# Main.net
KiCad netlist of a schematic drawn in Altium Designer
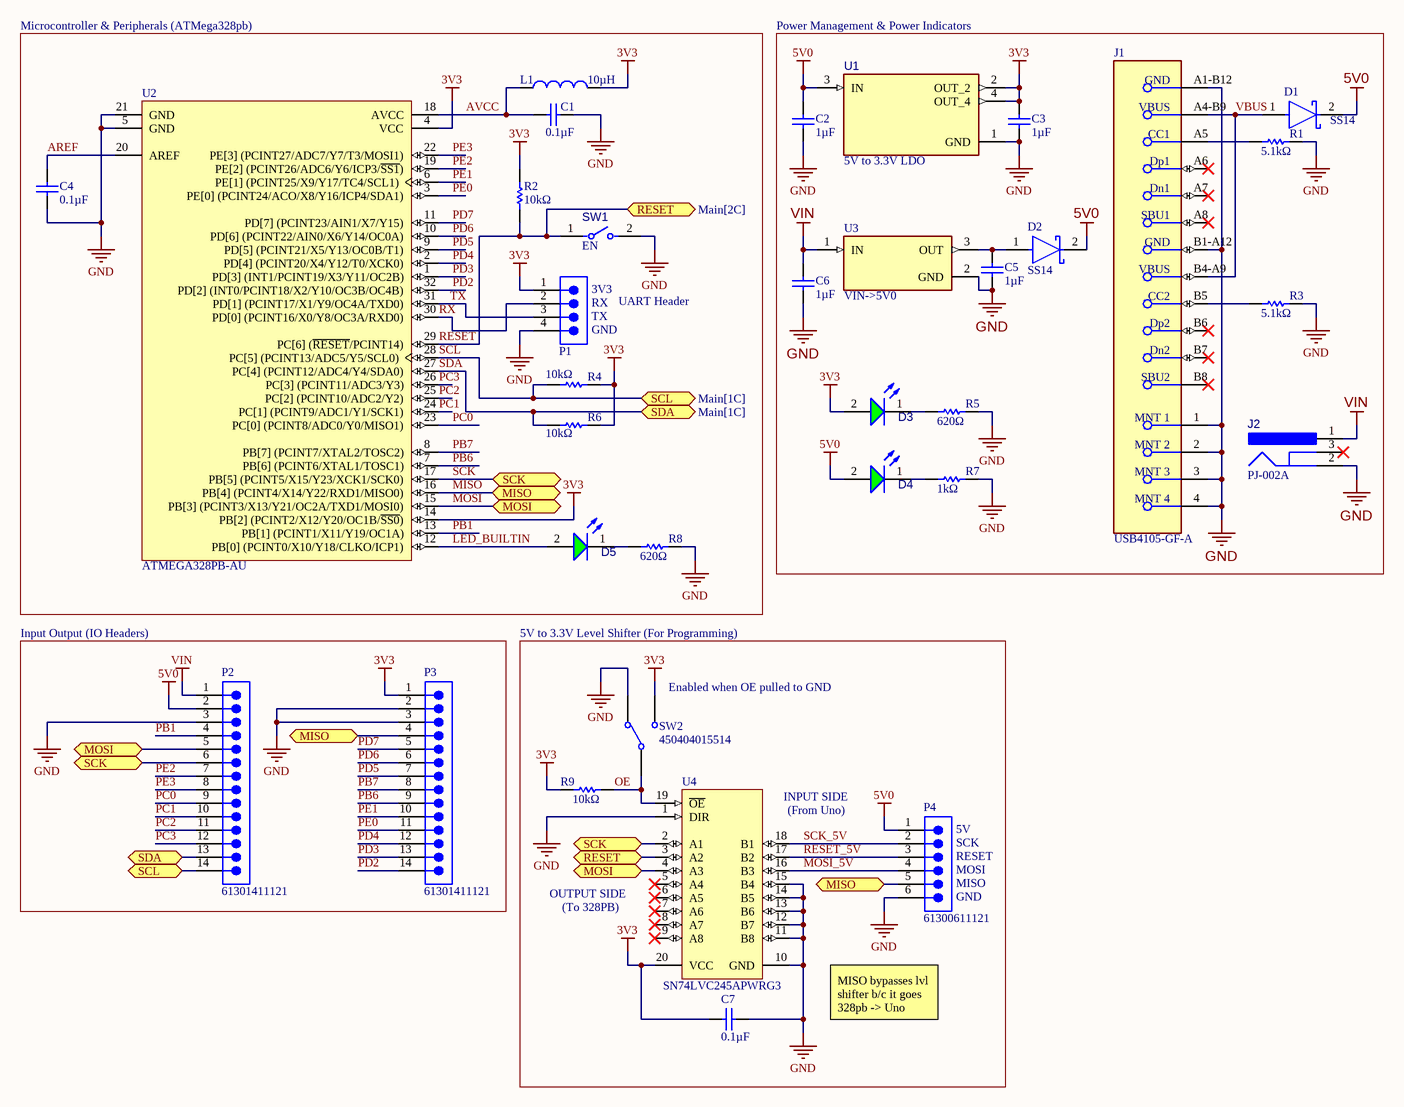
[diagram p0: Main.SchDoc]

(export (version "E")
  (design (tool "Eeschema 10.0.6"))
  (components
    (comp (ref "C1")
      (value "0.1µF")
      (footprint "CAPC3216X100X50LL20T25")
      (description "Chip Capacitor, 100 nF, +/- 10%, 25 V, -55 to 125 degC, 1206 (3216 Metric), RoHS, Tape and Reel")
      (fields (field (name "MANUFACTURER") "Kemet"))
      (libsource (lib "") (part "CAP-NP-2_1"))
    )
    (comp (ref "C2")
      (value "1µF")
      (footprint "CAPC3216X110X50LL20T25")
      (description "Chip Capacitor, 1 uF, +/- 10%, 50 V, -55 to 125 degC, 1206 (3216 Metric), RoHS, Tape and Reel")
      (fields (field (name "MANUFACTURER") "Kemet") (field (name "TOLERANCE") "10%"))
      (libsource (lib "Altium Content Vault") (part "CAP-NP-2"))
    )
    (comp (ref "C3")
      (value "1µF")
      (footprint "CAPC3216X110X50LL20T25")
      (description "Chip Capacitor, 1 uF, +/- 10%, 50 V, -55 to 125 degC, 1206 (3216 Metric), RoHS, Tape and Reel")
      (fields (field (name "MANUFACTURER") "Kemet") (field (name "TOLERANCE") "10%"))
      (libsource (lib "Altium Content Vault") (part "CAP-NP-2"))
    )
    (comp (ref "C4")
      (value "0.1µF")
      (footprint "CAPC3216X100X50LL20T25")
      (description "Chip Capacitor, 100 nF, +/- 10%, 25 V, -55 to 125 degC, 1206 (3216 Metric), RoHS, Tape and Reel")
      (fields (field (name "MANUFACTURER") "Kemet"))
      (libsource (lib "") (part "CAP-NP-2_1"))
    )
    (comp (ref "C5")
      (value "1µF")
      (footprint "CAPC3216X110X50LL20T25")
      (description "Chip Capacitor, 1 uF, +/- 10%, 50 V, -55 to 125 degC, 1206 (3216 Metric), RoHS, Tape and Reel")
      (fields (field (name "MANUFACTURER") "Kemet") (field (name "TOLERANCE") "10%"))
      (libsource (lib "Altium Content Vault") (part "CAP-NP-2"))
    )
    (comp (ref "C6")
      (value "1µF")
      (footprint "CAPC3216X110X50LL20T25")
      (description "Chip Capacitor, 1 uF, +/- 10%, 50 V, -55 to 125 degC, 1206 (3216 Metric), RoHS, Tape and Reel")
      (fields (field (name "MANUFACTURER") "Kemet") (field (name "TOLERANCE") "10%"))
      (libsource (lib "Altium Content Vault") (part "CAP-NP-2"))
    )
    (comp (ref "C7")
      (value "0.1µF")
      (footprint "CAPC3216X100X50LL20T25")
      (description "Chip Capacitor, 100 nF, +/- 10%, 25 V, -55 to 125 degC, 1206 (3216 Metric), RoHS, Tape and Reel")
      (fields (field (name "MANUFACTURER") "Kemet"))
      (libsource (lib "") (part "CAP-NP-2_1"))
    )
    (comp (ref "D1")
      (value "SS14")
      (footprint "FP-403AE-MFG")
      (description "DIODE SCHOTTKY 40V 1A SMA")
      (fields
        (field (name "MANUFACTURER") "ON Semiconductor")
        (field (name "OCTOPART") "https://octopart.com/ss14-on+semiconductor-29205033")
      )
      (libsource (lib "Altium Content Vault") (part "360ad2f4ac25a952324d13796385471"))
    )
    (comp (ref "D2")
      (value "SS14")
      (footprint "FP-403AE-MFG")
      (description "DIODE SCHOTTKY 40V 1A SMA")
      (fields
        (field (name "MANUFACTURER") "ON Semiconductor")
        (field (name "OCTOPART") "https://octopart.com/ss14-on+semiconductor-29205033")
      )
      (libsource (lib "Altium Content Vault") (part "360ad2f4ac25a952324d13796385471"))
    )
    (comp (ref "D3")
      (value "150120GS75000")
      (footprint "WL-SMCW_1206_150120xx75000")
      (description "WL-SMCW SMT Mono-Color Chip LED Waterclear")
      (libsource (lib "Altium Content Vault") (part "LED_Green_2A-1K"))
    )
    (comp (ref "D4")
      (value "150120GS75000")
      (footprint "WL-SMCW_1206_150120xx75000")
      (description "WL-SMCW SMT Mono-Color Chip LED Waterclear")
      (libsource (lib "Altium Content Vault") (part "LED_Green_2A-1K"))
    )
    (comp (ref "D5")
      (value "150120GS75000")
      (footprint "WL-SMCW_1206_150120xx75000")
      (description "WL-SMCW SMT Mono-Color Chip LED Waterclear")
      (libsource (lib "Altium Content Vault") (part "LED_Green_2A-1K"))
    )
    (comp (ref "J1")
      (value "USB4105-GF-A")
      (footprint "FP-USB4105-GF-A-MFG")
      (description "CONN RCPT USB2.0 TYPEC 5A")
      (fields
        (field (name "MANUFACTURER") "GCT")
        (field (name "OCTOPART") "https://octopart.com/usb4105-gf-a-gct-106627878")
      )
      (libsource (lib "Altium Content Vault") (part "e7c17a616881a82b79941196b4bec10"))
    )
    (comp (ref "J2")
      (value "PJ-002A")
      (footprint "CUI-PJ-002A_V")
      (fields (field (name "MANUFACTURER") "CUIInc."))
      (libsource (lib "Altium Content Vault") (part "JACK-2CD3-RN_B"))
    )
    (comp (ref "L1")
      (value "10µH")
      (footprint "WE-MI_1206_L3.2W1.6H1.1")
      (fields (field (name "TOLERANCE") "10%"))
      (libsource (lib "Altium Content Vault") (part "Inductor - 1"))
    )
    (comp (ref "P1")
      (value "61300411121")
      (footprint "61300411121")
      (description "WR-PHD Pin Header, THT, Vertical, pitch 2.54mm, 1 Row, 4P")
      (fields (field (name "MANUFACTURER") "Wurth Elektronik"))
      (libsource (lib "Altium_WR-PHD_rev24a") (part "61300411121"))
    )
    (comp (ref "P2")
      (value "61301411121")
      (footprint "61301411121")
      (libsource (lib "Altium Content Vault") (part "Header_Male_1R_14P"))
    )
    (comp (ref "P3")
      (value "61301411121")
      (footprint "61301411121")
      (libsource (lib "Altium Content Vault") (part "Header_Male_1R_14P"))
    )
    (comp (ref "P4")
      (value "61300611121")
      (footprint "61300611121")
      (libsource (lib "Altium Content Vault") (part "Header_Male_1R_06P"))
    )
    (comp (ref "R1")
      (value "5.1kΩ")
      (footprint "RESC3116X65X40LL10T20")
      (fields (field (name "MANUFACTURER") "Yageo") (field (name "PART NUMBER") "RC1206JR-075K1L"))
      (libsource (lib "Altium Content Vault") (part "RES"))
    )
    (comp (ref "R2")
      (value "10kΩ")
      (footprint "RESC3116X65X40LL10T20")
      (description "Chip Resistor, 10 KOhm, +/- 1%, 0.25 W, -55 to 155 degC, 1206 (3216 Metric), RoHS, Tape and Reel")
      (fields (field (name "TOLERANCE") "1%") (field (name "MANUFACTURER") "Yageo"))
      (libsource (lib "Altium Content Vault") (part "RES-2"))
    )
    (comp (ref "R3")
      (value "5.1kΩ")
      (footprint "RESC3116X65X40LL10T20")
      (fields (field (name "MANUFACTURER") "Yageo") (field (name "PART NUMBER") "RC1206JR-075K1L"))
      (libsource (lib "Altium Content Vault") (part "RES"))
    )
    (comp (ref "R4")
      (value "10kΩ")
      (footprint "RESC3116X65X40LL10T20")
      (description "Chip Resistor, 10 KOhm, +/- 1%, 0.25 W, -55 to 155 degC, 1206 (3216 Metric), RoHS, Tape and Reel")
      (fields (field (name "TOLERANCE") "1%") (field (name "MANUFACTURER") "Yageo"))
      (libsource (lib "Altium Content Vault") (part "RES-2"))
    )
    (comp (ref "R5")
      (value "620Ω")
      (footprint "RESC3116X65X40LL10T20")
      (fields (field (name "PART NUMBER") "RC1206JR-07620RL") (field (name "MANUFACTURER") "Yageo"))
      (libsource (lib "Altium Content Vault") (part "RES"))
    )
    (comp (ref "R6")
      (value "10kΩ")
      (footprint "RESC3116X65X40LL10T20")
      (description "Chip Resistor, 10 KOhm, +/- 1%, 0.25 W, -55 to 155 degC, 1206 (3216 Metric), RoHS, Tape and Reel")
      (fields (field (name "TOLERANCE") "1%") (field (name "MANUFACTURER") "Yageo"))
      (libsource (lib "Altium Content Vault") (part "RES-2"))
    )
    (comp (ref "R7")
      (value "1kΩ")
      (footprint "RESC3116X65X40LL10T20")
      (description "Chip Resistor, 1 KOhm, +/- 1%, 0.25 W, -55 to 155 degC, 1206 (3216 Metric), RoHS, Tape and Reel")
      (fields (field (name "TOLERANCE") "1%") (field (name "MANUFACTURER") "Yageo"))
      (libsource (lib "Altium Content Vault") (part "RES-2"))
    )
    (comp (ref "R8")
      (value "620Ω")
      (footprint "RESC3116X65X40LL10T20")
      (fields (field (name "PART NUMBER") "RC1206JR-07620RL") (field (name "MANUFACTURER") "Yageo"))
      (libsource (lib "Altium Content Vault") (part "RES"))
    )
    (comp (ref "R9")
      (value "10kΩ")
      (footprint "RESC3116X65X40LL10T20")
      (description "Chip Resistor, 10 KOhm, +/- 1%, 0.25 W, -55 to 155 degC, 1206 (3216 Metric), RoHS, Tape and Reel")
      (fields (field (name "TOLERANCE") "1%") (field (name "MANUFACTURER") "Yageo"))
      (libsource (lib "Altium Content Vault") (part "RES-2"))
    )
    (comp (ref "SW1")
      (value "EN")
      (footprint "FP-B3U-1000P-B-MFG")
      (description "SWITCH TACTILE SPST-NO 0.05A 12V")
      (fields
        (field (name "MANUFACTURER PART NUMBER") "B3U-1000P-B")
        (field (name "OCTOPART") "https://octopart.com/b3u-1000p-b-omron-1057356")
      )
      (libsource (lib "Altium Content Vault") (part "bb27bde45df87f1f469753f287ef5ae"))
    )
    (comp (ref "SW2")
      (value "450404015514")
      (footprint "450404015514")
      (description "450404015514 Slide Switch, 0.3A, 5Vdc, Smd Rohs Compliant: Yes")
      (libsource (lib "Altium Content Vault") (part "SPDT"))
    )
    (comp (ref "U1")
      (value "TLV1117LV33DCYR")
      (footprint "VREG_TLV1117LV33DCYR")
      (description "1-A, low-dropout voltage regulator")
      (fields (field (name "DIGI-KEY_PART_NUMBER") "296-28778-2-ND") (field (name "MF") "Texas Instruments"))
      (libsource (lib "TLV1117LV33DCYR") (part "TLV1117LV33DCYR"))
    )
    (comp (ref "U2")
      (value "ATMEGA328PB-AU")
      (footprint "ATML-32A_L")
      (fields (field (name "MANUFACTURER") "Microchip"))
      (libsource (lib "Altium Content Vault") (part "ATML-ATMEGA328PB-32A"))
    )
    (comp (ref "U3")
      (value "VIN->5V0")
      (footprint "DPAK229P990X238-4N")
      (description "Linear Voltage Regulator IC 1 Output 1A DPAK")
      (fields (field (name "MP") "MC7805BDTRKG") (field (name "MF") "ON Semiconductor"))
      (libsource (lib "MC7805BDTRKG") (part "MC7805BDTRKG"))
    )
    (comp (ref "U4")
      (value "SN74LVC245APWRG3")
      (footprint "PW0020A_N")
      (description "Octal Bus Transceiver With 3-State Outputs, PW0020A, LARGE T&R")
      (fields
        (field (name "MANUFACTURER") "Texas Instruments")
        (field (name "GENERIC PART NUMBER") "SN74LVC245A")
      )
      (libsource (lib "Altium Content Vault") (part "TI-SN_CDX4XXXXXX245XX_6XXX-20"))
    )
  )
  (nets
    (net (code "1") (name "/AREF") (class "Default")
      (node (ref "C4") (pin "1") (pinfunction "1_1") (pintype "passive"))
      (node (ref "U2") (pin "20") (pinfunction "AREF_20") (pintype "passive"))
    )
    (net (code "2") (name "/AVCC") (class "Default")
      (node (ref "C1") (pin "2") (pinfunction "2_2") (pintype "passive"))
      (node (ref "L1") (pin "1") (pinfunction "1_1") (pintype "passive"))
      (node (ref "U2") (pin "18") (pinfunction "AVCC_18") (pintype "power_in"))
    )
    (net (code "3") (name "/LED_BUILTIN") (class "Default")
      (node (ref "D5") (pin "2") (pinfunction "A_2") (pintype "passive"))
      (node (ref "U2") (pin "12") (pinfunction "PB[0]_(PCINT0/X10/Y18/CLKO/ICP1)_12") (pintype "bidirectional"))
    )
    (net (code "4") (name "/MISO") (class "Default")
      (node (ref "P3") (pin "4") (pinfunction "4_4") (pintype "passive"))
      (node (ref "P4") (pin "5") (pinfunction "5_5") (pintype "passive"))
      (node (ref "U2") (pin "16") (pinfunction "PB[4]_(PCINT4/X14/Y22/RXD1/MISO0)_16") (pintype "bidirectional"))
    )
    (net (code "5") (name "/MOSI") (class "Default")
      (node (ref "P2") (pin "5") (pinfunction "5_5") (pintype "passive"))
      (node (ref "U2") (pin "15") (pinfunction "PB[3]_(PCINT3/X13/Y21/OC2A/TXD1/MOSI0)_15") (pintype "bidirectional"))
      (node (ref "U4") (pin "4") (pinfunction "A3_4") (pintype "bidirectional"))
    )
    (net (code "6") (name "/MOSI_5V") (class "Default")
      (node (ref "P4") (pin "4") (pinfunction "4_4") (pintype "passive"))
      (node (ref "U4") (pin "16") (pinfunction "B3_16") (pintype "bidirectional"))
    )
    (net (code "7") (name "/OE") (class "Default")
      (node (ref "R9") (pin "1") (pinfunction "1_1") (pintype "passive"))
      (node (ref "SW2") (pin "COM") (pinfunction "COM_COM") (pintype "passive"))
      (node (ref "U4") (pin "19") (pinfunction "~{OE}_19") (pintype "input"))
    )
    (net (code "8") (name "/PB1") (class "Default")
      (node (ref "P2") (pin "4") (pinfunction "4_4") (pintype "passive"))
      (node (ref "U2") (pin "13") (pinfunction "PB[1]_(PCINT1/X11/Y19/OC1A)_13") (pintype "bidirectional"))
    )
    (net (code "9") (name "/PB6") (class "Default")
      (node (ref "P3") (pin "9") (pinfunction "9_9") (pintype "passive"))
      (node (ref "U2") (pin "7") (pinfunction "PB[6]_(PCINT6/XTAL1/TOSC1)_7") (pintype "bidirectional"))
    )
    (net (code "10") (name "/PB7") (class "Default")
      (node (ref "P3") (pin "8") (pinfunction "8_8") (pintype "passive"))
      (node (ref "U2") (pin "8") (pinfunction "PB[7]_(PCINT7/XTAL2/TOSC2)_8") (pintype "bidirectional"))
    )
    (net (code "11") (name "/PC0") (class "Default")
      (node (ref "P2") (pin "9") (pinfunction "9_9") (pintype "passive"))
      (node (ref "U2") (pin "23") (pinfunction "PC[0]_(PCINT8/ADC0/Y0/MISO1)_23") (pintype "bidirectional"))
    )
    (net (code "12") (name "/PC1") (class "Default")
      (node (ref "P2") (pin "10") (pinfunction "10_10") (pintype "passive"))
      (node (ref "U2") (pin "24") (pinfunction "PC[1]_(PCINT9/ADC1/Y1/SCK1)_24") (pintype "bidirectional"))
    )
    (net (code "13") (name "/PC2") (class "Default")
      (node (ref "P2") (pin "11") (pinfunction "11_11") (pintype "passive"))
      (node (ref "U2") (pin "25") (pinfunction "PC[2]_(PCINT10/ADC2/Y2)_25") (pintype "bidirectional"))
    )
    (net (code "14") (name "/PC3") (class "Default")
      (node (ref "P2") (pin "12") (pinfunction "12_12") (pintype "passive"))
      (node (ref "U2") (pin "26") (pinfunction "PC[3]_(PCINT11/ADC3/Y3)_26") (pintype "bidirectional"))
    )
    (net (code "15") (name "/PD2") (class "Default")
      (node (ref "P3") (pin "14") (pinfunction "14_14") (pintype "passive"))
      (node (ref "U2") (pin "32") (pinfunction "PD[2]_(INT0/PCINT18/X2/Y10/OC3B/OC4B)_32") (pintype "bidirectional"))
    )
    (net (code "16") (name "/PD3") (class "Default")
      (node (ref "P3") (pin "13") (pinfunction "13_13") (pintype "passive"))
      (node (ref "U2") (pin "1") (pinfunction "PD[3]_(INT1/PCINT19/X3/Y11/OC2B)_1") (pintype "bidirectional"))
    )
    (net (code "17") (name "/PD4") (class "Default")
      (node (ref "P3") (pin "12") (pinfunction "12_12") (pintype "passive"))
      (node (ref "U2") (pin "2") (pinfunction "PD[4]_(PCINT20/X4/Y12/T0/XCK0)_2") (pintype "bidirectional"))
    )
    (net (code "18") (name "/PD5") (class "Default")
      (node (ref "P3") (pin "7") (pinfunction "7_7") (pintype "passive"))
      (node (ref "U2") (pin "9") (pinfunction "PD[5]_(PCINT21/X5/Y13/OC0B/T1)_9") (pintype "bidirectional"))
    )
    (net (code "19") (name "/PD6") (class "Default")
      (node (ref "P3") (pin "6") (pinfunction "6_6") (pintype "passive"))
      (node (ref "U2") (pin "10") (pinfunction "PD[6]_(PCINT22/AIN0/X6/Y14/OC0A)_10") (pintype "bidirectional"))
    )
    (net (code "20") (name "/PD7") (class "Default")
      (node (ref "P3") (pin "5") (pinfunction "5_5") (pintype "passive"))
      (node (ref "U2") (pin "11") (pinfunction "PD[7]_(PCINT23/AIN1/X7/Y15)_11") (pintype "bidirectional"))
    )
    (net (code "21") (name "/PE0") (class "Default")
      (node (ref "P3") (pin "11") (pinfunction "11_11") (pintype "passive"))
      (node (ref "U2") (pin "3") (pinfunction "PE[0]_(PCINT24/ACO/X8/Y16/ICP4/SDA1)_3") (pintype "bidirectional"))
    )
    (net (code "22") (name "/PE1") (class "Default")
      (node (ref "P3") (pin "10") (pinfunction "10_10") (pintype "passive"))
      (node (ref "U2") (pin "6") (pinfunction "PE[1]_(PCINT25/X9/Y17/TC4/SCL1)_6") (pintype "bidirectional"))
    )
    (net (code "23") (name "/PE2") (class "Default")
      (node (ref "P2") (pin "7") (pinfunction "7_7") (pintype "passive"))
      (node (ref "U2") (pin "19") (pinfunction "PE[2]_(PCINT26/ADC6/Y6/ICP3/~{SS1})_19") (pintype "bidirectional"))
    )
    (net (code "24") (name "/PE3") (class "Default")
      (node (ref "P2") (pin "8") (pinfunction "8_8") (pintype "passive"))
      (node (ref "U2") (pin "22") (pinfunction "PE[3]_(PCINT27/ADC7/Y7/T3/MOSI1)_22") (pintype "bidirectional"))
    )
    (net (code "25") (name "/RESET") (class "Default")
      (node (ref "R2") (pin "1") (pinfunction "1_1") (pintype "passive"))
      (node (ref "SW1") (pin "1") (pinfunction "1_1") (pintype "passive"))
      (node (ref "U2") (pin "29") (pinfunction "PC[6]_(~{RESET}/PCINT14)_29") (pintype "bidirectional"))
      (node (ref "U4") (pin "3") (pinfunction "A2_3") (pintype "bidirectional"))
    )
    (net (code "26") (name "/RESET_5V") (class "Default")
      (node (ref "P4") (pin "3") (pinfunction "3_3") (pintype "passive"))
      (node (ref "U4") (pin "17") (pinfunction "B2_17") (pintype "bidirectional"))
    )
    (net (code "27") (name "/RX") (class "Default")
      (node (ref "P1") (pin "2") (pinfunction "2_2") (pintype "passive"))
      (node (ref "U2") (pin "30") (pinfunction "PD[0]_(PCINT16/X0/Y8/OC3A/RXD0)_30") (pintype "bidirectional"))
    )
    (net (code "28") (name "/SCK") (class "Default")
      (node (ref "P2") (pin "6") (pinfunction "6_6") (pintype "passive"))
      (node (ref "U2") (pin "17") (pinfunction "PB[5]_(PCINT5/X15/Y23/XCK1/SCK0)_17") (pintype "bidirectional"))
      (node (ref "U4") (pin "2") (pinfunction "A1_2") (pintype "bidirectional"))
    )
    (net (code "29") (name "/SCK_5V") (class "Default")
      (node (ref "P4") (pin "2") (pinfunction "2_2") (pintype "passive"))
      (node (ref "U4") (pin "18") (pinfunction "B1_18") (pintype "bidirectional"))
    )
    (net (code "30") (name "/SCL") (class "Default")
      (node (ref "P2") (pin "14") (pinfunction "14_14") (pintype "passive"))
      (node (ref "R4") (pin "1") (pinfunction "1_1") (pintype "passive"))
      (node (ref "U2") (pin "28") (pinfunction "PC[5]_(PCINT13/ADC5/Y5/SCL0)_28") (pintype "bidirectional"))
    )
    (net (code "31") (name "/SDA") (class "Default")
      (node (ref "P2") (pin "13") (pinfunction "13_13") (pintype "passive"))
      (node (ref "R6") (pin "1") (pinfunction "1_1") (pintype "passive"))
      (node (ref "U2") (pin "27") (pinfunction "PC[4]_(PCINT12/ADC4/Y4/SDA0)_27") (pintype "bidirectional"))
    )
    (net (code "32") (name "/TX") (class "Default")
      (node (ref "P1") (pin "3") (pinfunction "3_3") (pintype "passive"))
      (node (ref "U2") (pin "31") (pinfunction "PD[1]_(PCINT17/X1/Y9/OC4A/TXD0)_31") (pintype "bidirectional"))
    )
    (net (code "33") (name "/VBUS") (class "Default")
      (node (ref "D1") (pin "1") (pinfunction "A_1") (pintype "passive"))
      (node (ref "J1") (pin "A4-B9") (pinfunction "VBUS_A4-B9") (pintype "power_in"))
      (node (ref "J1") (pin "B4-A9") (pinfunction "VBUS_B4-A9") (pintype "bidirectional"))
    )
    (net (code "34") (name "3V3") (class "Default")
      (node (ref "C3") (pin "2") (pinfunction "2_2") (pintype "passive"))
      (node (ref "C7") (pin "1") (pinfunction "1_1") (pintype "passive"))
      (node (ref "D3") (pin "2") (pinfunction "A_2") (pintype "passive"))
      (node (ref "L1") (pin "2") (pinfunction "2_2") (pintype "passive"))
      (node (ref "P1") (pin "1") (pinfunction "1_1") (pintype "passive"))
      (node (ref "P3") (pin "1") (pinfunction "1_1") (pintype "passive"))
      (node (ref "R2") (pin "2") (pinfunction "2_2") (pintype "passive"))
      (node (ref "R4") (pin "2") (pinfunction "2_2") (pintype "passive"))
      (node (ref "R6") (pin "2") (pinfunction "2_2") (pintype "passive"))
      (node (ref "R9") (pin "2") (pinfunction "2_2") (pintype "passive"))
      (node (ref "SW2") (pin "L2") (pinfunction "L2_L2") (pintype "passive"))
      (node (ref "U1") (pin "2") (pinfunction "OUT_2_2") (pintype "output"))
      (node (ref "U1") (pin "4") (pinfunction "OUT_4_4") (pintype "output"))
      (node (ref "U2") (pin "14") (pinfunction "PB[2]_(PCINT2/X12/Y20/OC1B/~{SS0})_14") (pintype "bidirectional"))
      (node (ref "U2") (pin "4") (pinfunction "VCC_4") (pintype "power_in"))
      (node (ref "U4") (pin "20") (pinfunction "VCC_20") (pintype "power_in"))
    )
    (net (code "35") (name "5V0") (class "Default")
      (node (ref "C2") (pin "2") (pinfunction "2_2") (pintype "passive"))
      (node (ref "D1") (pin "2") (pinfunction "C_2") (pintype "passive"))
      (node (ref "D2") (pin "2") (pinfunction "C_2") (pintype "passive"))
      (node (ref "D4") (pin "2") (pinfunction "A_2") (pintype "passive"))
      (node (ref "P2") (pin "2") (pinfunction "2_2") (pintype "passive"))
      (node (ref "P4") (pin "1") (pinfunction "1_1") (pintype "passive"))
      (node (ref "U1") (pin "3") (pinfunction "IN_3") (pintype "input"))
    )
    (net (code "36") (name "GND") (class "Default")
      (node (ref "C1") (pin "1") (pinfunction "1_1") (pintype "passive"))
      (node (ref "C2") (pin "1") (pinfunction "1_1") (pintype "passive"))
      (node (ref "C3") (pin "1") (pinfunction "1_1") (pintype "passive"))
      (node (ref "C4") (pin "2") (pinfunction "2_2") (pintype "passive"))
      (node (ref "C5") (pin "1") (pinfunction "1_1") (pintype "passive"))
      (node (ref "C6") (pin "1") (pinfunction "1_1") (pintype "passive"))
      (node (ref "C7") (pin "2") (pinfunction "2_2") (pintype "passive"))
      (node (ref "J1") (pin "1") (pinfunction "MNT_1_1") (pintype "power_in"))
      (node (ref "J1") (pin "2") (pinfunction "MNT_2_2") (pintype "power_in"))
      (node (ref "J1") (pin "3") (pinfunction "MNT_3_3") (pintype "power_in"))
      (node (ref "J1") (pin "4") (pinfunction "MNT_4_4") (pintype "power_in"))
      (node (ref "J1") (pin "A1-B12") (pinfunction "GND_A1-B12") (pintype "power_in"))
      (node (ref "J1") (pin "B1-A12") (pinfunction "GND_B1-A12") (pintype "bidirectional"))
      (node (ref "J2") (pin "2") (pinfunction "2_2") (pintype "passive"))
      (node (ref "P1") (pin "4") (pinfunction "4_4") (pintype "passive"))
      (node (ref "P2") (pin "3") (pinfunction "3_3") (pintype "passive"))
      (node (ref "P3") (pin "2") (pinfunction "2_2") (pintype "passive"))
      (node (ref "P3") (pin "3") (pinfunction "3_3") (pintype "passive"))
      (node (ref "P4") (pin "6") (pinfunction "6_6") (pintype "passive"))
      (node (ref "R1") (pin "1") (pinfunction "1_1") (pintype "passive"))
      (node (ref "R3") (pin "2") (pinfunction "2_2") (pintype "passive"))
      (node (ref "R5") (pin "2") (pinfunction "2_2") (pintype "passive"))
      (node (ref "R7") (pin "2") (pinfunction "2_2") (pintype "passive"))
      (node (ref "R8") (pin "2") (pinfunction "2_2") (pintype "passive"))
      (node (ref "SW1") (pin "2") (pinfunction "2_2") (pintype "passive"))
      (node (ref "SW2") (pin "L1") (pinfunction "L1_L1") (pintype "passive"))
      (node (ref "U1") (pin "1") (pinfunction "GND_1") (pintype "power_in"))
      (node (ref "U2") (pin "21") (pinfunction "GND_21") (pintype "power_in"))
      (node (ref "U2") (pin "5") (pinfunction "GND_5") (pintype "power_in"))
      (node (ref "U3") (pin "2") (pinfunction "GND_2") (pintype "power_in"))
      (node (ref "U4") (pin "1") (pinfunction "DIR_1") (pintype "input"))
      (node (ref "U4") (pin "10") (pinfunction "GND_10") (pintype "power_in"))
      (node (ref "U4") (pin "11") (pinfunction "B8_11") (pintype "bidirectional"))
      (node (ref "U4") (pin "12") (pinfunction "B7_12") (pintype "bidirectional"))
      (node (ref "U4") (pin "13") (pinfunction "B6_13") (pintype "bidirectional"))
      (node (ref "U4") (pin "14") (pinfunction "B5_14") (pintype "bidirectional"))
      (node (ref "U4") (pin "15") (pinfunction "B4_15") (pintype "bidirectional"))
    )
    (net (code "37") (name "Net-(D2-A)") (class "Default")
      (node (ref "C5") (pin "2") (pinfunction "2_2") (pintype "passive"))
      (node (ref "D2") (pin "1") (pinfunction "A_1") (pintype "passive"))
      (node (ref "U3") (pin "3") (pinfunction "OUT_3") (pintype "output"))
    )
    (net (code "38") (name "Net-(D3-K)") (class "Default")
      (node (ref "D3") (pin "1") (pinfunction "K_1") (pintype "passive"))
      (node (ref "R5") (pin "1") (pinfunction "1_1") (pintype "passive"))
    )
    (net (code "39") (name "Net-(D4-K)") (class "Default")
      (node (ref "D4") (pin "1") (pinfunction "K_1") (pintype "passive"))
      (node (ref "R7") (pin "1") (pinfunction "1_1") (pintype "passive"))
    )
    (net (code "40") (name "Net-(D5-K)") (class "Default")
      (node (ref "D5") (pin "1") (pinfunction "K_1") (pintype "passive"))
      (node (ref "R8") (pin "1") (pinfunction "1_1") (pintype "passive"))
    )
    (net (code "41") (name "Net-(J1-CC1)") (class "Default")
      (node (ref "J1") (pin "A5") (pinfunction "CC1_A5") (pintype "power_in"))
      (node (ref "R1") (pin "2") (pinfunction "2_2") (pintype "passive"))
    )
    (net (code "42") (name "Net-(J1-CC2)") (class "Default")
      (node (ref "J1") (pin "B5") (pinfunction "CC2_B5") (pintype "bidirectional"))
      (node (ref "R3") (pin "1") (pinfunction "1_1") (pintype "passive"))
    )
    (net (code "43") (name "VIN") (class "Default")
      (node (ref "C6") (pin "2") (pinfunction "2_2") (pintype "passive"))
      (node (ref "J2") (pin "1") (pinfunction "1_1") (pintype "passive"))
      (node (ref "P2") (pin "1") (pinfunction "1_1") (pintype "passive"))
      (node (ref "U3") (pin "1") (pinfunction "IN_1") (pintype "input"))
    )
    (net (code "44") (name "unconnected-(J1-Dn1-PadA7)") (class "Default")
      (node (ref "J1") (pin "A7") (pinfunction "Dn1_A7") (pintype "bidirectional+no_connect"))
    )
    (net (code "45") (name "unconnected-(J1-Dn2-PadB7)") (class "Default")
      (node (ref "J1") (pin "B7") (pinfunction "Dn2_B7") (pintype "bidirectional+no_connect"))
    )
    (net (code "46") (name "unconnected-(J1-Dp1-PadA6)") (class "Default")
      (node (ref "J1") (pin "A6") (pinfunction "Dp1_A6") (pintype "bidirectional+no_connect"))
    )
    (net (code "47") (name "unconnected-(J1-Dp2-PadB6)") (class "Default")
      (node (ref "J1") (pin "B6") (pinfunction "Dp2_B6") (pintype "bidirectional+no_connect"))
    )
    (net (code "48") (name "unconnected-(J1-SBU1-PadA8)") (class "Default")
      (node (ref "J1") (pin "A8") (pinfunction "SBU1_A8") (pintype "bidirectional+no_connect"))
    )
    (net (code "49") (name "unconnected-(J1-SBU2-PadB8)") (class "Default")
      (node (ref "J1") (pin "B8") (pinfunction "SBU2_B8") (pintype "power_in+no_connect"))
    )
    (net (code "50") (name "unconnected-(J2-Pad3)") (class "Default")
      (node (ref "J2") (pin "3") (pinfunction "3_3") (pintype "passive+no_connect"))
    )
    (net (code "51") (name "unconnected-(U4-A4-Pad5)") (class "Default")
      (node (ref "U4") (pin "5") (pinfunction "A4_5") (pintype "bidirectional+no_connect"))
    )
    (net (code "52") (name "unconnected-(U4-A5-Pad6)") (class "Default")
      (node (ref "U4") (pin "6") (pinfunction "A5_6") (pintype "bidirectional+no_connect"))
    )
    (net (code "53") (name "unconnected-(U4-A6-Pad7)") (class "Default")
      (node (ref "U4") (pin "7") (pinfunction "A6_7") (pintype "bidirectional+no_connect"))
    )
    (net (code "54") (name "unconnected-(U4-A7-Pad8)") (class "Default")
      (node (ref "U4") (pin "8") (pinfunction "A7_8") (pintype "bidirectional+no_connect"))
    )
    (net (code "55") (name "unconnected-(U4-A8-Pad9)") (class "Default")
      (node (ref "U4") (pin "9") (pinfunction "A8_9") (pintype "bidirectional+no_connect"))
    )
  )
)
